# DifferenceAmplifier.net
KiCad netlist of a schematic drawn in Altium Designer
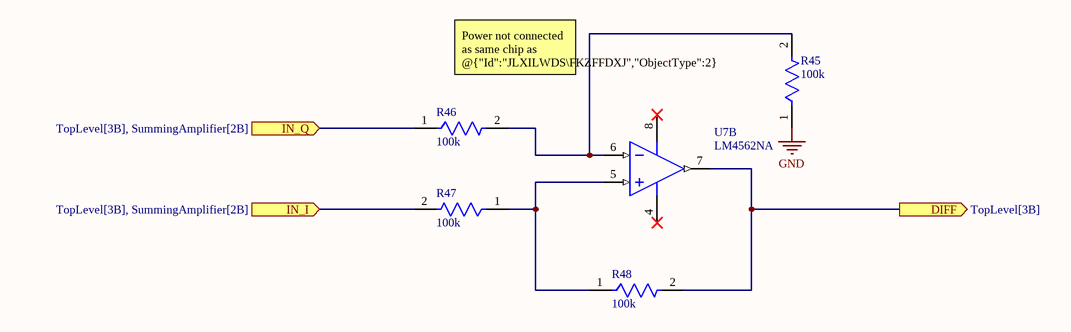
[diagram p0: DifferenceAmplifier.SchDoc]

(export (version "E")
  (design (tool "Eeschema 10.0.6"))
  (components
    (comp (ref "R45")
      (value "100k")
      (footprint "FP-RC0805-0_6-IPC_C")
      (description "RES 100K OHM 1% 1/8W 0805")
      (fields (field (name "TOLERANCE") "1%"))
      (libsource (lib "Altium Content Vault") (part "1029c3af85768c4190bb7ad29bc67b5"))
    )
    (comp (ref "R46")
      (value "100k")
      (footprint "FP-RC0805-0_6-IPC_C")
      (description "RES 100K OHM 1% 1/8W 0805")
      (fields (field (name "TOLERANCE") "1%"))
      (libsource (lib "Altium Content Vault") (part "1029c3af85768c4190bb7ad29bc67b5"))
    )
    (comp (ref "R47")
      (value "100k")
      (footprint "FP-RC0805-0_6-IPC_C")
      (description "RES 100K OHM 1% 1/8W 0805")
      (fields (field (name "TOLERANCE") "1%"))
      (libsource (lib "Altium Content Vault") (part "1029c3af85768c4190bb7ad29bc67b5"))
    )
    (comp (ref "R48")
      (value "100k")
      (footprint "FP-RC0805-0_6-IPC_C")
      (description "RES 100K OHM 1% 1/8W 0805")
      (fields (field (name "TOLERANCE") "1%"))
      (libsource (lib "Altium Content Vault") (part "1029c3af85768c4190bb7ad29bc67b5"))
    )
    (comp (ref "U7")
      (value "LM4562NA")
      (footprint "N08E")
      (description "Dual High Performance, High Fidelity Audio Operational Amplifier, 8-pin MDIP")
      (fields (field (name "MANUFACTURER") "National Semiconductor"))
      (libsource (lib "Altium Content Vault") (part "AMP-AUDA-LM4562-8"))
    )
  )
  (nets
    (net (code "1") (name "/DIFF") (class "Default")
      (node (ref "R48") (pin "2") (pinfunction "2_2") (pintype "passive"))
      (node (ref "U7") (pin "7") (pinfunction "OUT_B_7") (pintype "output"))
    )
    (net (code "2") (name "/IN_I") (class "Default")
      (node (ref "R47") (pin "2") (pinfunction "2_2") (pintype "passive"))
    )
    (net (code "3") (name "/IN_Q") (class "Default")
      (node (ref "R46") (pin "1") (pinfunction "1_1") (pintype "passive"))
    )
    (net (code "4") (name "GND") (class "Default")
      (node (ref "R45") (pin "1") (pinfunction "1_1") (pintype "passive"))
    )
    (net (code "5") (name "Net-(R45-Pad2)") (class "Default")
      (node (ref "R45") (pin "2") (pinfunction "2_2") (pintype "passive"))
      (node (ref "R46") (pin "2") (pinfunction "2_2") (pintype "passive"))
      (node (ref "U7") (pin "6") (pinfunction "IN_B_6") (pintype "input"))
    )
    (net (code "6") (name "Net-(R47-Pad1)") (class "Default")
      (node (ref "R47") (pin "1") (pinfunction "1_1") (pintype "passive"))
      (node (ref "R48") (pin "1") (pinfunction "1_1") (pintype "passive"))
      (node (ref "U7") (pin "5") (pinfunction "IN_B_5") (pintype "input"))
    )
    (net (code "7") (name "unconnected-(U7B-V+-Pad8)") (class "Default")
      (node (ref "U7") (pin "8") (pinfunction "V+_8") (pintype "power_in+no_connect"))
    )
    (net (code "8") (name "unconnected-(U7B-V--Pad4)") (class "Default")
      (node (ref "U7") (pin "4") (pinfunction "V-_4") (pintype "power_in+no_connect"))
    )
  )
)
